# output.net
KiCad netlist of a schematic drawn in EAGLE
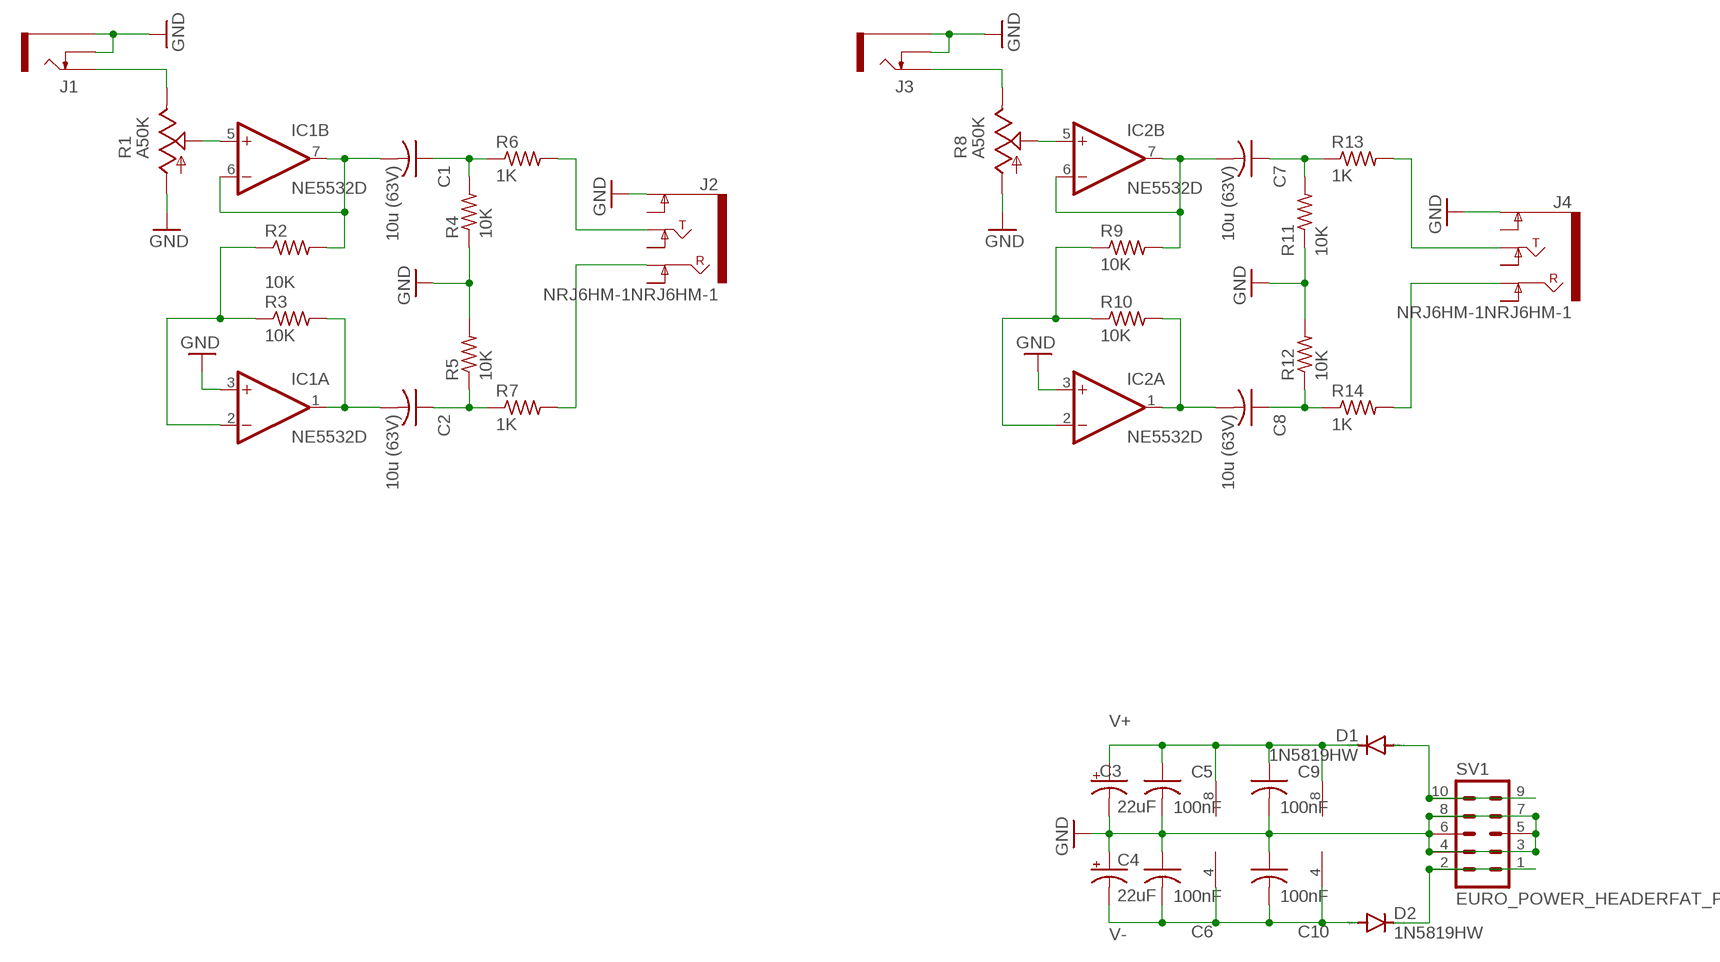
[diagram p0: schematic, sheet 1]

(export (version "E")
  (design (tool "Eeschema 10.0.6"))
  (components
    (comp (ref "C1")
      (value "10u (63V)")
      (footprint "eagle-import:C1210")
      (libsource (lib "eagle-import") (part "C-USC1210"))
    )
    (comp (ref "C2")
      (value "10u (63V)")
      (footprint "eagle-import:C1210")
      (libsource (lib "eagle-import") (part "C-USC1210"))
    )
    (comp (ref "C3")
      (value "22uF")
      (footprint "eagle-import:PANASONIC_B")
      (libsource (lib "eagle-import") (part "CPOL-USB"))
    )
    (comp (ref "C4")
      (value "22uF")
      (footprint "eagle-import:PANASONIC_B")
      (libsource (lib "eagle-import") (part "CPOL-USB"))
    )
    (comp (ref "C5")
      (value "100nF")
      (footprint "eagle-import:C0805")
      (libsource (lib "eagle-import") (part "C-USC0805"))
    )
    (comp (ref "C6")
      (value "100nF")
      (footprint "eagle-import:C0805")
      (libsource (lib "eagle-import") (part "C-USC0805"))
    )
    (comp (ref "C7")
      (value "10u (63V)")
      (footprint "eagle-import:C1210")
      (libsource (lib "eagle-import") (part "C-USC1210"))
    )
    (comp (ref "C8")
      (value "10u (63V)")
      (footprint "eagle-import:C1210")
      (libsource (lib "eagle-import") (part "C-USC1210"))
    )
    (comp (ref "C9")
      (value "100nF")
      (footprint "eagle-import:C0805")
      (libsource (lib "eagle-import") (part "C-USC0805"))
    )
    (comp (ref "C10")
      (value "100nF")
      (footprint "eagle-import:C0805")
      (libsource (lib "eagle-import") (part "C-USC0805"))
    )
    (comp (ref "D1")
      (value "1N5819HW")
      (footprint "eagle-import:SOD123")
      (libsource (lib "eagle-import") (part "DIODE-SOD123"))
    )
    (comp (ref "D2")
      (value "1N5819HW")
      (footprint "eagle-import:SOD123")
      (libsource (lib "eagle-import") (part "DIODE-SOD123"))
    )
    (comp (ref "IC1")
      (value "NE5532D")
      (footprint "eagle-import:SO08")
      (libsource (lib "eagle-import") (part "NE5532D"))
    )
    (comp (ref "IC2")
      (value "NE5532D")
      (footprint "eagle-import:SO08")
      (libsource (lib "eagle-import") (part "NE5532D"))
    )
    (comp (ref "J1")
      (value "PJ302M")
      (footprint "eagle-import:PJ302M")
      (libsource (lib "eagle-import") (part "PJ302M"))
    )
    (comp (ref "J2")
      (value "NRJ6HM-1NRJ6HM-1")
      (footprint "eagle-import:NRJ6HM-1")
      (libsource (lib "eagle-import") (part "NRJ6HM-1NRJ6HM-1"))
    )
    (comp (ref "J3")
      (value "PJ302M")
      (footprint "eagle-import:PJ302M")
      (libsource (lib "eagle-import") (part "PJ302M"))
    )
    (comp (ref "J4")
      (value "NRJ6HM-1NRJ6HM-1")
      (footprint "eagle-import:NRJ6HM-1")
      (libsource (lib "eagle-import") (part "NRJ6HM-1NRJ6HM-1"))
    )
    (comp (ref "R1")
      (value "A50K")
      (footprint "eagle-import:ALPHA_9MM_POT_RIGHT_ANGLE")
      (libsource (lib "eagle-import") (part "ALPHA_9MM_POT_RIGHT_ANGLE"))
    )
    (comp (ref "R2")
      (value "10K")
      (footprint "eagle-import:R0805")
      (libsource (lib "eagle-import") (part "R-US_R0805"))
    )
    (comp (ref "R3")
      (value "10K")
      (footprint "eagle-import:R0805")
      (libsource (lib "eagle-import") (part "R-US_R0805"))
    )
    (comp (ref "R4")
      (value "10K")
      (footprint "eagle-import:R0805")
      (libsource (lib "eagle-import") (part "R-US_R0805"))
    )
    (comp (ref "R5")
      (value "10K")
      (footprint "eagle-import:R0805")
      (libsource (lib "eagle-import") (part "R-US_R0805"))
    )
    (comp (ref "R6")
      (value "1K")
      (footprint "eagle-import:R0805")
      (libsource (lib "eagle-import") (part "R-US_R0805"))
    )
    (comp (ref "R7")
      (value "1K")
      (footprint "eagle-import:R0805")
      (libsource (lib "eagle-import") (part "R-US_R0805"))
    )
    (comp (ref "R8")
      (value "A50K")
      (footprint "eagle-import:ALPHA_9MM_POT_RIGHT_ANGLE")
      (libsource (lib "eagle-import") (part "ALPHA_9MM_POT_RIGHT_ANGLE"))
    )
    (comp (ref "R9")
      (value "10K")
      (footprint "eagle-import:R0805")
      (libsource (lib "eagle-import") (part "R-US_R0805"))
    )
    (comp (ref "R10")
      (value "10K")
      (footprint "eagle-import:R0805")
      (libsource (lib "eagle-import") (part "R-US_R0805"))
    )
    (comp (ref "R11")
      (value "10K")
      (footprint "eagle-import:R0805")
      (libsource (lib "eagle-import") (part "R-US_R0805"))
    )
    (comp (ref "R12")
      (value "10K")
      (footprint "eagle-import:R0805")
      (libsource (lib "eagle-import") (part "R-US_R0805"))
    )
    (comp (ref "R13")
      (value "1K")
      (footprint "eagle-import:R0805")
      (libsource (lib "eagle-import") (part "R-US_R0805"))
    )
    (comp (ref "R14")
      (value "1K")
      (footprint "eagle-import:R0805")
      (libsource (lib "eagle-import") (part "R-US_R0805"))
    )
    (comp (ref "SV1")
      (value "EURO_POWER_HEADERFAT_PADS")
      (footprint "eagle-import:EURO_PWR_HEADER_FAT")
      (libsource (lib "eagle-import") (part "EURO_POWER_HEADERFAT_PADS"))
    )
  )
  (nets
    (net (code "1") (name "/V+") (class "Default")
      (node (ref "C3") (pin "+") (pinfunction "+_+") (pintype "passive"))
      (node (ref "C5") (pin "1") (pinfunction "1_1") (pintype "passive"))
      (node (ref "C9") (pin "1") (pinfunction "1_1") (pintype "passive"))
      (node (ref "D1") (pin "C") (pinfunction "C_C") (pintype "passive"))
      (node (ref "IC1") (pin "8") (pinfunction "V+_8") (pintype "power_in"))
      (node (ref "IC2") (pin "8") (pinfunction "V+_8") (pintype "power_in"))
    )
    (net (code "2") (name "/V-") (class "Default")
      (node (ref "C10") (pin "2") (pinfunction "2_2") (pintype "passive"))
      (node (ref "C4") (pin "-") (pinfunction "-_-") (pintype "passive"))
      (node (ref "C6") (pin "2") (pinfunction "2_2") (pintype "passive"))
      (node (ref "D2") (pin "A") (pinfunction "A_A") (pintype "passive"))
      (node (ref "IC1") (pin "4") (pinfunction "V-_4") (pintype "power_in"))
      (node (ref "IC2") (pin "4") (pinfunction "V-_4") (pintype "power_in"))
    )
    (net (code "3") (name "GND") (class "Default")
      (node (ref "C10") (pin "1") (pinfunction "1_1") (pintype "passive"))
      (node (ref "C3") (pin "-") (pinfunction "-_-") (pintype "passive"))
      (node (ref "C4") (pin "+") (pinfunction "+_+") (pintype "passive"))
      (node (ref "C5") (pin "2") (pinfunction "2_2") (pintype "passive"))
      (node (ref "C6") (pin "1") (pinfunction "1_1") (pintype "passive"))
      (node (ref "C9") (pin "2") (pinfunction "2_2") (pintype "passive"))
      (node (ref "IC1") (pin "3") (pinfunction "+IN_3") (pintype "input"))
      (node (ref "IC2") (pin "3") (pinfunction "+IN_3") (pintype "input"))
      (node (ref "J1") (pin "GND") (pinfunction "SLEEVE_GND") (pintype "passive"))
      (node (ref "J1") (pin "SW") (pinfunction "SWITCH_SW") (pintype "passive"))
      (node (ref "J2") (pin "SLEEVE") (pinfunction "EARTH_SLEEVE") (pintype "bidirectional"))
      (node (ref "J3") (pin "GND") (pinfunction "SLEEVE_GND") (pintype "passive"))
      (node (ref "J3") (pin "SW") (pinfunction "SWITCH_SW") (pintype "passive"))
      (node (ref "J4") (pin "SLEEVE") (pinfunction "EARTH_SLEEVE") (pintype "bidirectional"))
      (node (ref "R1") (pin "1") (pinfunction "A_1") (pintype "passive"))
      (node (ref "R11") (pin "1") (pinfunction "1_1") (pintype "passive"))
      (node (ref "R12") (pin "2") (pinfunction "2_2") (pintype "passive"))
      (node (ref "R4") (pin "1") (pinfunction "1_1") (pintype "passive"))
      (node (ref "R5") (pin "2") (pinfunction "2_2") (pintype "passive"))
      (node (ref "R8") (pin "1") (pinfunction "A_1") (pintype "passive"))
      (node (ref "SV1") (pin "3") (pinfunction "3_3") (pintype "passive"))
      (node (ref "SV1") (pin "4") (pinfunction "4_4") (pintype "passive"))
      (node (ref "SV1") (pin "5") (pinfunction "5_5") (pintype "passive"))
      (node (ref "SV1") (pin "6") (pinfunction "6_6") (pintype "passive"))
      (node (ref "SV1") (pin "7") (pinfunction "7_7") (pintype "passive"))
      (node (ref "SV1") (pin "8") (pinfunction "8_8") (pintype "passive"))
    )
    (net (code "4") (name "Net-(C1-Pad1)") (class "Default")
      (node (ref "C1") (pin "1") (pinfunction "1_1") (pintype "passive"))
      (node (ref "R4") (pin "2") (pinfunction "2_2") (pintype "passive"))
      (node (ref "R6") (pin "1") (pinfunction "1_1") (pintype "passive"))
    )
    (net (code "5") (name "Net-(C2-Pad1)") (class "Default")
      (node (ref "C2") (pin "1") (pinfunction "1_1") (pintype "passive"))
      (node (ref "R5") (pin "1") (pinfunction "1_1") (pintype "passive"))
      (node (ref "R7") (pin "1") (pinfunction "1_1") (pintype "passive"))
    )
    (net (code "6") (name "Net-(C7-Pad1)") (class "Default")
      (node (ref "C7") (pin "1") (pinfunction "1_1") (pintype "passive"))
      (node (ref "R11") (pin "2") (pinfunction "2_2") (pintype "passive"))
      (node (ref "R13") (pin "1") (pinfunction "1_1") (pintype "passive"))
    )
    (net (code "7") (name "Net-(C8-Pad1)") (class "Default")
      (node (ref "C8") (pin "1") (pinfunction "1_1") (pintype "passive"))
      (node (ref "R12") (pin "1") (pinfunction "1_1") (pintype "passive"))
      (node (ref "R14") (pin "1") (pinfunction "1_1") (pintype "passive"))
    )
    (net (code "8") (name "Net-(D1-PadA)") (class "Default")
      (node (ref "D1") (pin "A") (pinfunction "A_A") (pintype "passive"))
      (node (ref "SV1") (pin "10") (pinfunction "10_10") (pintype "passive"))
      (node (ref "SV1") (pin "9") (pinfunction "9_9") (pintype "passive"))
    )
    (net (code "9") (name "Net-(D2-PadC)") (class "Default")
      (node (ref "D2") (pin "C") (pinfunction "C_C") (pintype "passive"))
      (node (ref "SV1") (pin "1") (pinfunction "1_1") (pintype "passive"))
      (node (ref "SV1") (pin "2") (pinfunction "2_2") (pintype "passive"))
    )
    (net (code "10") (name "Net-(IC1A--IN)") (class "Default")
      (node (ref "IC1") (pin "2") (pinfunction "-IN_2") (pintype "input"))
      (node (ref "R2") (pin "1") (pinfunction "1_1") (pintype "passive"))
      (node (ref "R3") (pin "1") (pinfunction "1_1") (pintype "passive"))
    )
    (net (code "11") (name "Net-(IC1A-OUT)") (class "Default")
      (node (ref "C2") (pin "2") (pinfunction "2_2") (pintype "passive"))
      (node (ref "IC1") (pin "1") (pinfunction "OUT_1") (pintype "output"))
      (node (ref "R3") (pin "2") (pinfunction "2_2") (pintype "passive"))
    )
    (net (code "12") (name "Net-(IC1B-+IN)") (class "Default")
      (node (ref "IC1") (pin "5") (pinfunction "+IN_5") (pintype "input"))
      (node (ref "R1") (pin "2") (pinfunction "S_2") (pintype "passive"))
    )
    (net (code "13") (name "Net-(IC1B--IN)") (class "Default")
      (node (ref "C1") (pin "2") (pinfunction "2_2") (pintype "passive"))
      (node (ref "IC1") (pin "6") (pinfunction "-IN_6") (pintype "input"))
      (node (ref "IC1") (pin "7") (pinfunction "OUT_7") (pintype "output"))
      (node (ref "R2") (pin "2") (pinfunction "2_2") (pintype "passive"))
    )
    (net (code "14") (name "Net-(IC2A--IN)") (class "Default")
      (node (ref "IC2") (pin "2") (pinfunction "-IN_2") (pintype "input"))
      (node (ref "R10") (pin "1") (pinfunction "1_1") (pintype "passive"))
      (node (ref "R9") (pin "1") (pinfunction "1_1") (pintype "passive"))
    )
    (net (code "15") (name "Net-(IC2A-OUT)") (class "Default")
      (node (ref "C8") (pin "2") (pinfunction "2_2") (pintype "passive"))
      (node (ref "IC2") (pin "1") (pinfunction "OUT_1") (pintype "output"))
      (node (ref "R10") (pin "2") (pinfunction "2_2") (pintype "passive"))
    )
    (net (code "16") (name "Net-(IC2B-+IN)") (class "Default")
      (node (ref "IC2") (pin "5") (pinfunction "+IN_5") (pintype "input"))
      (node (ref "R8") (pin "2") (pinfunction "S_2") (pintype "passive"))
    )
    (net (code "17") (name "Net-(IC2B--IN)") (class "Default")
      (node (ref "C7") (pin "2") (pinfunction "2_2") (pintype "passive"))
      (node (ref "IC2") (pin "6") (pinfunction "-IN_6") (pintype "input"))
      (node (ref "IC2") (pin "7") (pinfunction "OUT_7") (pintype "output"))
      (node (ref "R9") (pin "2") (pinfunction "2_2") (pintype "passive"))
    )
    (net (code "18") (name "Net-(J2-PadRING)") (class "Default")
      (node (ref "J2") (pin "RING") (pinfunction "RING_RING") (pintype "bidirectional"))
      (node (ref "R7") (pin "2") (pinfunction "2_2") (pintype "passive"))
    )
    (net (code "19") (name "Net-(J2-PadTIP)") (class "Default")
      (node (ref "J2") (pin "TIP") (pinfunction "TIP_TIP") (pintype "bidirectional"))
      (node (ref "R6") (pin "2") (pinfunction "2_2") (pintype "passive"))
    )
    (net (code "20") (name "Net-(J4-PadRING)") (class "Default")
      (node (ref "J4") (pin "RING") (pinfunction "RING_RING") (pintype "bidirectional"))
      (node (ref "R14") (pin "2") (pinfunction "2_2") (pintype "passive"))
    )
    (net (code "21") (name "Net-(J4-PadTIP)") (class "Default")
      (node (ref "J4") (pin "TIP") (pinfunction "TIP_TIP") (pintype "bidirectional"))
      (node (ref "R13") (pin "2") (pinfunction "2_2") (pintype "passive"))
    )
    (net (code "22") (name "Net-(R1-E)") (class "Default")
      (node (ref "J1") (pin "TIP") (pinfunction "TIP_TIP") (pintype "passive"))
      (node (ref "R1") (pin "3") (pinfunction "E_3") (pintype "passive"))
    )
    (net (code "23") (name "Net-(R8-E)") (class "Default")
      (node (ref "J3") (pin "TIP") (pinfunction "TIP_TIP") (pintype "passive"))
      (node (ref "R8") (pin "3") (pinfunction "E_3") (pintype "passive"))
    )
    (net (code "24") (name "unconnected-(J2-EARTH-NORM-PadSLEEVE-NORM)") (class "Default")
      (node (ref "J2") (pin "SLEEVE-NORM") (pinfunction "EARTH-NORM_SLEEVE-NORM") (pintype "bidirectional"))
    )
    (net (code "25") (name "unconnected-(J2-PadRING-NORM)") (class "Default")
      (node (ref "J2") (pin "RING-NORM") (pinfunction "RING-NORM_RING-NORM") (pintype "bidirectional"))
    )
    (net (code "26") (name "unconnected-(J2-PadTIP-NORM)") (class "Default")
      (node (ref "J2") (pin "TIP-NORM") (pinfunction "TIP-NORM_TIP-NORM") (pintype "bidirectional"))
    )
    (net (code "27") (name "unconnected-(J4-EARTH-NORM-PadSLEEVE-NORM)") (class "Default")
      (node (ref "J4") (pin "SLEEVE-NORM") (pinfunction "EARTH-NORM_SLEEVE-NORM") (pintype "bidirectional"))
    )
    (net (code "28") (name "unconnected-(J4-PadRING-NORM)") (class "Default")
      (node (ref "J4") (pin "RING-NORM") (pinfunction "RING-NORM_RING-NORM") (pintype "bidirectional"))
    )
    (net (code "29") (name "unconnected-(J4-PadTIP-NORM)") (class "Default")
      (node (ref "J4") (pin "TIP-NORM") (pinfunction "TIP-NORM_TIP-NORM") (pintype "bidirectional"))
    )
  )
)
